# MAIN_BOARD_01.net
KiCad netlist of a schematic drawn in EAGLE
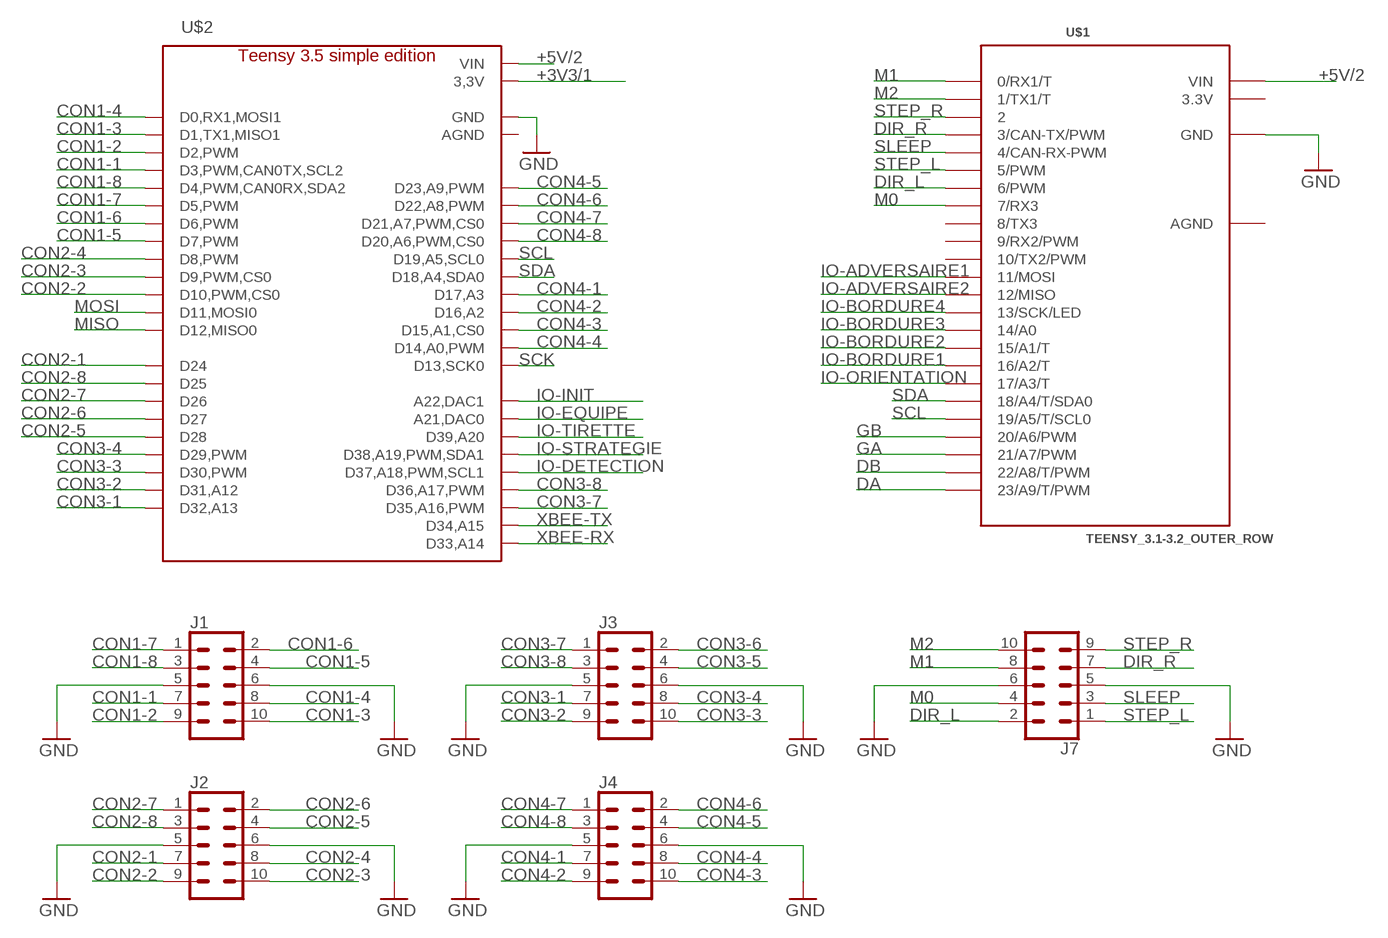
[diagram p0: schematic, sheet 1]
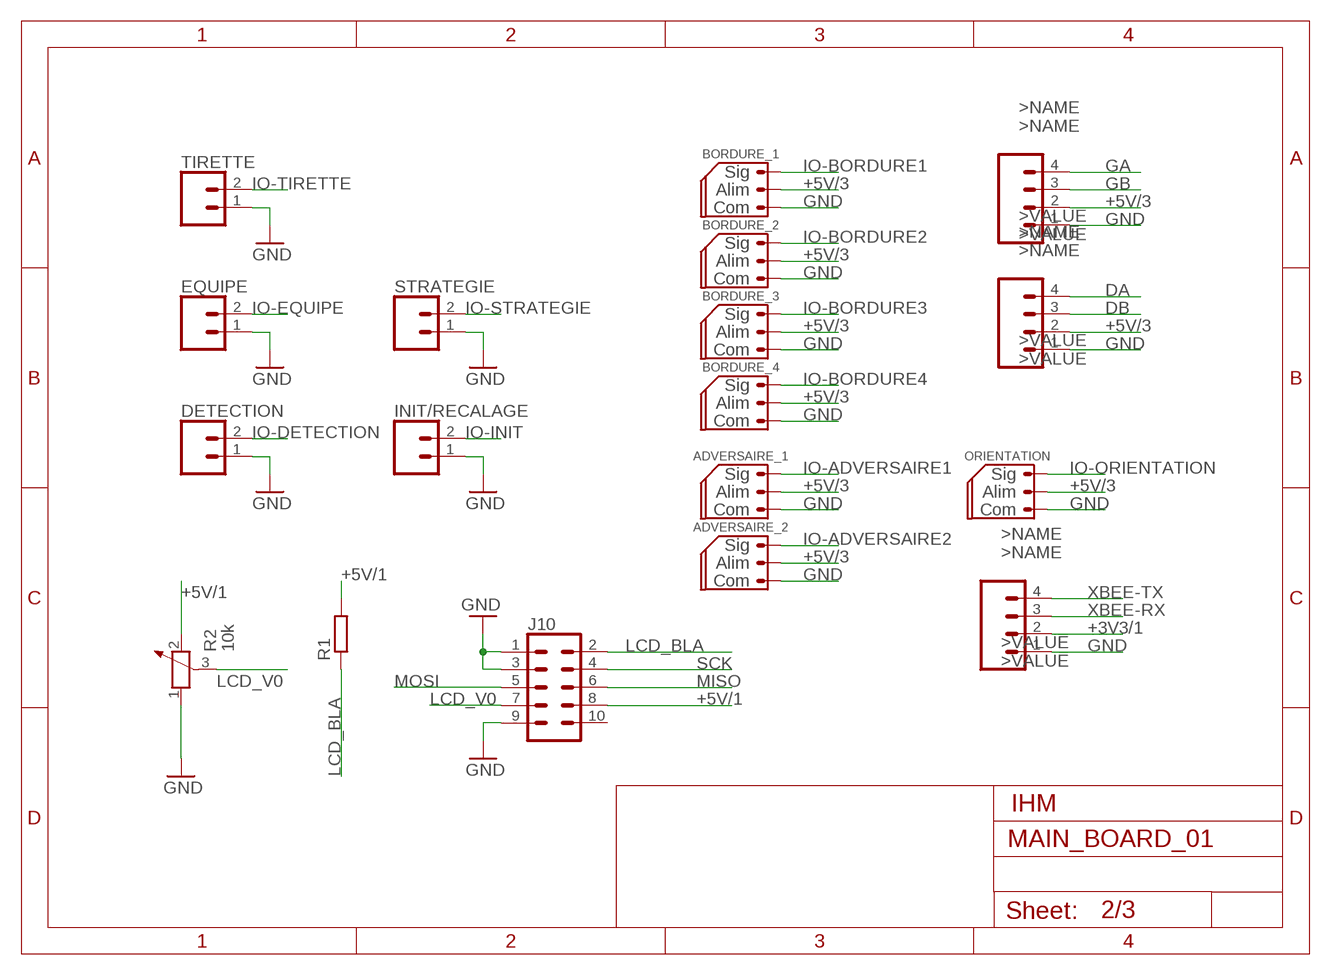
[diagram p1: schematic, sheet 2]
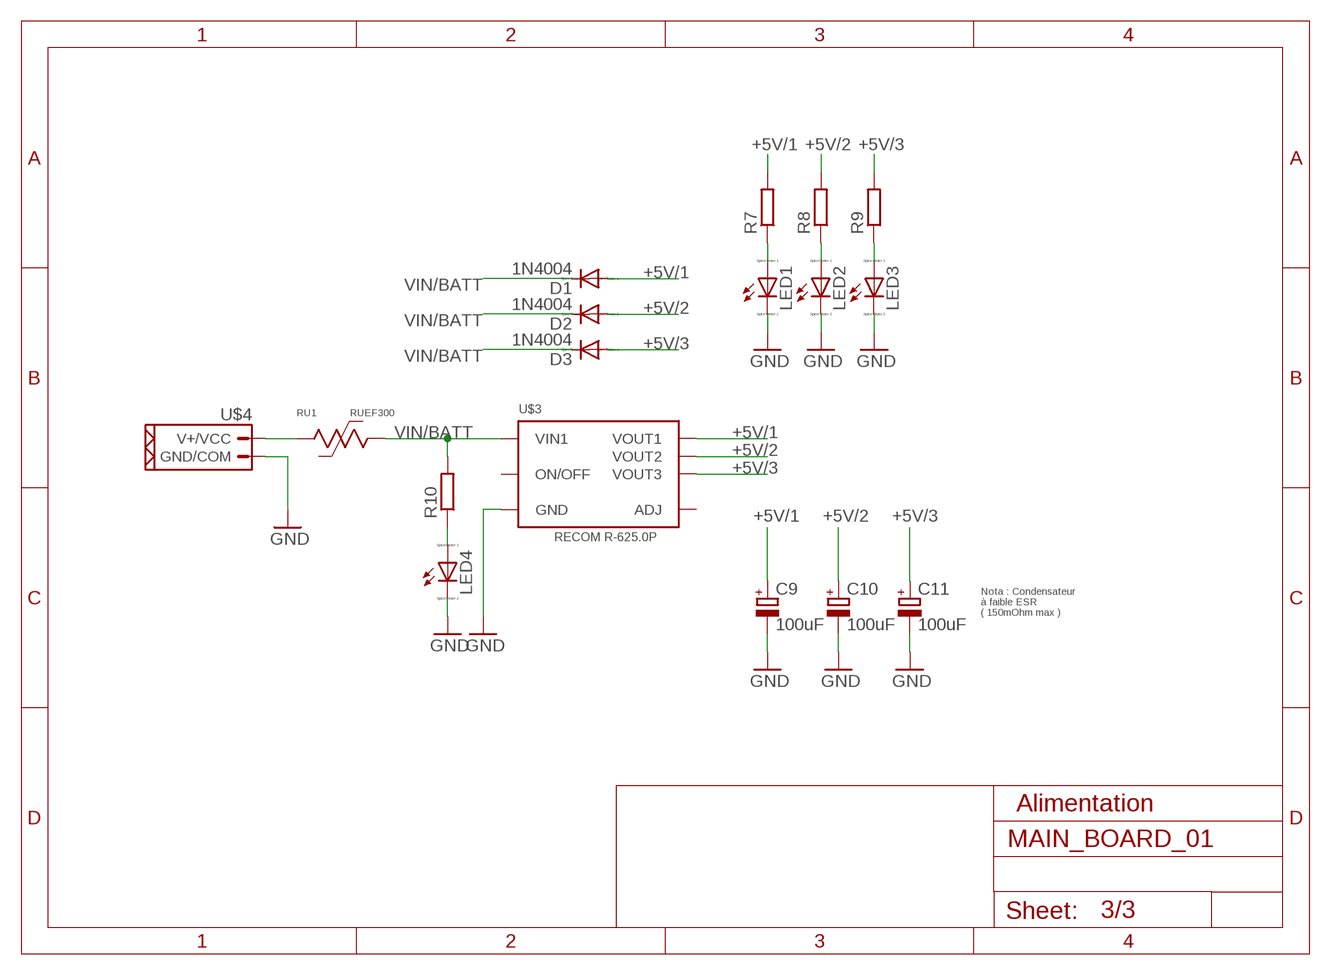
[diagram p2: schematic, sheet 3]

(export (version "E")
  (design (tool "Eeschema 10.0.6"))
  (components
    (comp (ref "J1")
      (value "CONN_05X2SHD")
      (footprint "eagle-import:2X5-SHROUDED")
      (libsource (lib "eagle-import") (part "CONN_05X2SHD"))
    )
    (comp (ref "J2")
      (value "CONN_05X2SHD")
      (footprint "eagle-import:2X5-SHROUDED")
      (libsource (lib "eagle-import") (part "CONN_05X2SHD"))
    )
    (comp (ref "J3")
      (value "CONN_05X2SHD")
      (footprint "eagle-import:2X5-SHROUDED")
      (libsource (lib "eagle-import") (part "CONN_05X2SHD"))
    )
    (comp (ref "J4")
      (value "CONN_05X2SHD")
      (footprint "eagle-import:2X5-SHROUDED")
      (libsource (lib "eagle-import") (part "CONN_05X2SHD"))
    )
    (comp (ref "J7")
      (value "CONN_05X2SHD")
      (footprint "eagle-import:2X5-SHROUDED")
      (libsource (lib "eagle-import") (part "CONN_05X2SHD"))
    )
    (comp (ref "U$1")
      (value "TEENSY_3.1-3.2_OUTER_ROW")
      (footprint "eagle-import:TEENSY_3.0-3.2&LC_OUTER_ROW")
      (libsource (lib "eagle-import") (part "TEENSY_3.1-3.2_OUTER_ROW"))
    )
    (comp (ref "U$2")
      (value "TEENSY_3.5")
      (footprint "eagle-import:TEENSY_3.5_LIGHT")
      (libsource (lib "eagle-import") (part "TEENSY_3.5"))
    )
    (comp (ref "C9")
      (value "100uF")
      (footprint "eagle-import:E5-10,5")
      (libsource (lib "eagle-import") (part "CPOL-EUE5-10.5"))
    )
    (comp (ref "C10")
      (value "100uF")
      (footprint "eagle-import:E5-10,5")
      (libsource (lib "eagle-import") (part "CPOL-EUE5-10.5"))
    )
    (comp (ref "C11")
      (value "100uF")
      (footprint "eagle-import:E5-10,5")
      (libsource (lib "eagle-import") (part "CPOL-EUE5-10.5"))
    )
    (comp (ref "D1")
      (value "1N4004")
      (footprint "eagle-import:DO41-10")
      (libsource (lib "eagle-import") (part "1N4004"))
    )
    (comp (ref "D2")
      (value "1N4004")
      (footprint "eagle-import:DO41-10")
      (libsource (lib "eagle-import") (part "1N4004"))
    )
    (comp (ref "D3")
      (value "1N4004")
      (footprint "eagle-import:DO41-10")
      (libsource (lib "eagle-import") (part "1N4004"))
    )
    (comp (ref "LED1")
      (value "LED_E")
      (footprint "eagle-import:LED_1206")
      (libsource (lib "eagle-import") (part "LED_E"))
    )
    (comp (ref "LED2")
      (value "LED_E")
      (footprint "eagle-import:LED_1206")
      (libsource (lib "eagle-import") (part "LED_E"))
    )
    (comp (ref "LED3")
      (value "LED_E")
      (footprint "eagle-import:LED_1206")
      (libsource (lib "eagle-import") (part "LED_E"))
    )
    (comp (ref "LED4")
      (value "LED_E")
      (footprint "eagle-import:LED_1206")
      (libsource (lib "eagle-import") (part "LED_E"))
    )
    (comp (ref "R7")
      (value "R-EU_R1206")
      (footprint "eagle-import:R1206")
      (libsource (lib "eagle-import") (part "R-EU_R1206"))
    )
    (comp (ref "R8")
      (value "R-EU_R1206")
      (footprint "eagle-import:R1206")
      (libsource (lib "eagle-import") (part "R-EU_R1206"))
    )
    (comp (ref "R9")
      (value "R-EU_R1206")
      (footprint "eagle-import:R1206")
      (libsource (lib "eagle-import") (part "R-EU_R1206"))
    )
    (comp (ref "R10")
      (value "R-EU_R1206")
      (footprint "eagle-import:R1206")
      (libsource (lib "eagle-import") (part "R-EU_R1206"))
    )
    (comp (ref "RU1")
      (value "RUEF300")
      (footprint "eagle-import:RUEF300")
      (libsource (lib "eagle-import") (part "RUEF300"))
    )
    (comp (ref "U$3")
      (value "R-625.0P")
      (footprint "eagle-import:R-6XXXP")
      (libsource (lib "eagle-import") (part "R-625.0P"))
    )
    (comp (ref "U$4")
      (value "CONN_02_PUI")
      (footprint "eagle-import:NSK396-2C")
      (libsource (lib "eagle-import") (part "CONN_02_PUI"))
    )
    (comp (ref "ADVERSAIRE_1")
      (value "CONN_03_SERVO")
      (footprint "eagle-import:MOLEX-1X3")
      (libsource (lib "eagle-import") (part "CONN_03_SERVO"))
    )
    (comp (ref "ADVERSAIRE_2")
      (value "CONN_03_SERVO")
      (footprint "eagle-import:MOLEX-1X3")
      (libsource (lib "eagle-import") (part "CONN_03_SERVO"))
    )
    (comp (ref "BORDURE_1")
      (value "CONN_03_SERVO")
      (footprint "eagle-import:MOLEX-1X3")
      (libsource (lib "eagle-import") (part "CONN_03_SERVO"))
    )
    (comp (ref "BORDURE_2")
      (value "CONN_03_SERVO")
      (footprint "eagle-import:MOLEX-1X3")
      (libsource (lib "eagle-import") (part "CONN_03_SERVO"))
    )
    (comp (ref "BORDURE_3")
      (value "CONN_03_SERVO")
      (footprint "eagle-import:MOLEX-1X3")
      (libsource (lib "eagle-import") (part "CONN_03_SERVO"))
    )
    (comp (ref "BORDURE_4")
      (value "CONN_03_SERVO")
      (footprint "eagle-import:MOLEX-1X3")
      (libsource (lib "eagle-import") (part "CONN_03_SERVO"))
    )
    (comp (ref "DETECTION")
      (value "CONN_02POLAR")
      (footprint "eagle-import:MOLEX-1X2")
      (libsource (lib "eagle-import") (part "CONN_02POLAR"))
    )
    (comp (ref "ENC_DROIT")
      (value "CONN_04POLAR")
      (footprint "eagle-import:MOLEX-1X4")
      (libsource (lib "eagle-import") (part "CONN_04POLAR"))
    )
    (comp (ref "ENC_DROIT1")
      (value "CONN_04POLAR")
      (footprint "eagle-import:MOLEX-1X4")
      (libsource (lib "eagle-import") (part "CONN_04POLAR"))
    )
    (comp (ref "ENC_GAUCHE")
      (value "CONN_04POLAR")
      (footprint "eagle-import:MOLEX-1X4")
      (libsource (lib "eagle-import") (part "CONN_04POLAR"))
    )
    (comp (ref "EQUIPE")
      (value "CONN_02POLAR")
      (footprint "eagle-import:MOLEX-1X2")
      (libsource (lib "eagle-import") (part "CONN_02POLAR"))
    )
    (comp (ref "INIT/RECALAGE")
      (value "CONN_02POLAR")
      (footprint "eagle-import:MOLEX-1X2")
      (libsource (lib "eagle-import") (part "CONN_02POLAR"))
    )
    (comp (ref "J10")
      (value "CONN_05X2SHD")
      (footprint "eagle-import:2X5-SHROUDED")
      (libsource (lib "eagle-import") (part "CONN_05X2SHD"))
    )
    (comp (ref "ORIENTATION")
      (value "CONN_03_SERVO")
      (footprint "eagle-import:MOLEX-1X3")
      (libsource (lib "eagle-import") (part "CONN_03_SERVO"))
    )
    (comp (ref "R1")
      (value "R-EU_R1206")
      (footprint "eagle-import:R1206")
      (libsource (lib "eagle-import") (part "R-EU_R1206"))
    )
    (comp (ref "R2")
      (value "10k")
      (footprint "eagle-import:PT-10")
      (libsource (lib "eagle-import") (part "POTENTIOMETER_PT-10"))
    )
    (comp (ref "STRATEGIE")
      (value "CONN_02POLAR")
      (footprint "eagle-import:MOLEX-1X2")
      (libsource (lib "eagle-import") (part "CONN_02POLAR"))
    )
    (comp (ref "TIRETTE")
      (value "CONN_02POLAR")
      (footprint "eagle-import:MOLEX-1X2")
      (libsource (lib "eagle-import") (part "CONN_02POLAR"))
    )
  )
  (nets
    (net (code "1") (name "+3V3{slash}1") (class "Default")
      (node (ref "ENC_DROIT1") (pin "2") (pinfunction "2_2") (pintype "passive"))
      (node (ref "U$2") (pin "P$15") (pinfunction "3,3V_P$15") (pintype "power_in"))
      (node (ref "U$2") (pin "P$46") (pinfunction "3,3V_P$46") (pintype "power_in"))
    )
    (net (code "2") (name "+5V{slash}1") (class "Default")
      (node (ref "C9") (pin "+") (pinfunction "+_+") (pintype "passive"))
      (node (ref "D1") (pin "A") (pinfunction "A_A") (pintype "passive"))
      (node (ref "J10") (pin "8") (pinfunction "8_8") (pintype "passive"))
      (node (ref "R1") (pin "2") (pinfunction "2_2") (pintype "passive"))
      (node (ref "R2") (pin "2") (pinfunction "2_2") (pintype "passive"))
      (node (ref "R7") (pin "2") (pinfunction "2_2") (pintype "passive"))
      (node (ref "U$3") (pin "P$9") (pinfunction "VOUT1_P$9") (pintype "power_in"))
    )
    (net (code "3") (name "+5V{slash}2") (class "Default")
      (node (ref "C10") (pin "+") (pinfunction "+_+") (pintype "passive"))
      (node (ref "D2") (pin "A") (pinfunction "A_A") (pintype "passive"))
      (node (ref "R8") (pin "2") (pinfunction "2_2") (pintype "passive"))
      (node (ref "U$1") (pin "V_IN") (pinfunction "VIN_V_IN") (pintype "power_in"))
      (node (ref "U$2") (pin "P$48") (pinfunction "VIN_P$48") (pintype "passive"))
      (node (ref "U$3") (pin "P$10") (pinfunction "VOUT2_P$10") (pintype "power_in"))
    )
    (net (code "4") (name "+5V{slash}3") (class "Default")
      (node (ref "ADVERSAIRE_1") (pin "2") (pinfunction "2_2") (pintype "passive"))
      (node (ref "ADVERSAIRE_2") (pin "2") (pinfunction "2_2") (pintype "passive"))
      (node (ref "BORDURE_1") (pin "2") (pinfunction "2_2") (pintype "passive"))
      (node (ref "BORDURE_2") (pin "2") (pinfunction "2_2") (pintype "passive"))
      (node (ref "BORDURE_3") (pin "2") (pinfunction "2_2") (pintype "passive"))
      (node (ref "BORDURE_4") (pin "2") (pinfunction "2_2") (pintype "passive"))
      (node (ref "C11") (pin "+") (pinfunction "+_+") (pintype "passive"))
      (node (ref "D3") (pin "A") (pinfunction "A_A") (pintype "passive"))
      (node (ref "ENC_DROIT") (pin "2") (pinfunction "2_2") (pintype "passive"))
      (node (ref "ENC_GAUCHE") (pin "2") (pinfunction "2_2") (pintype "passive"))
      (node (ref "ORIENTATION") (pin "2") (pinfunction "2_2") (pintype "passive"))
      (node (ref "R9") (pin "2") (pinfunction "2_2") (pintype "passive"))
      (node (ref "U$3") (pin "P$11") (pinfunction "VOUT3_P$11") (pintype "power_in"))
    )
    (net (code "5") (name "3.3V") (class "Default")
      (node (ref "U$1") (pin "3.3V") (pinfunction "3.3V_3.3V") (pintype "power_in"))
    )
    (net (code "6") (name "ADJ") (class "Default")
      (node (ref "U$3") (pin "P$12") (pinfunction "ADJ_P$12") (pintype "power_in"))
    )
    (net (code "7") (name "AGND") (class "Default")
      (node (ref "U$1") (pin "AGND") (pinfunction "AGND_AGND") (pintype "power_in"))
    )
    (net (code "8") (name "CON1-1") (class "Default")
      (node (ref "J1") (pin "7") (pinfunction "7_7") (pintype "passive"))
      (node (ref "U$2") (pin "P$5") (pinfunction "D3,PWM,CAN0TX,SCL2_P$5") (pintype "passive"))
    )
    (net (code "9") (name "CON1-2") (class "Default")
      (node (ref "J1") (pin "9") (pinfunction "9_9") (pintype "passive"))
      (node (ref "U$2") (pin "P$4") (pinfunction "D2,PWM_P$4") (pintype "passive"))
    )
    (net (code "10") (name "CON1-3") (class "Default")
      (node (ref "J1") (pin "10") (pinfunction "10_10") (pintype "passive"))
      (node (ref "U$2") (pin "P$3") (pinfunction "D1,TX1,MISO1_P$3") (pintype "passive"))
    )
    (net (code "11") (name "CON1-4") (class "Default")
      (node (ref "J1") (pin "8") (pinfunction "8_8") (pintype "passive"))
      (node (ref "U$2") (pin "P$2") (pinfunction "D0,RX1,MOSI1_P$2") (pintype "passive"))
    )
    (net (code "12") (name "CON1-5") (class "Default")
      (node (ref "J1") (pin "4") (pinfunction "4_4") (pintype "passive"))
      (node (ref "U$2") (pin "P$9") (pinfunction "D7,PWM_P$9") (pintype "passive"))
    )
    (net (code "13") (name "CON1-6") (class "Default")
      (node (ref "J1") (pin "2") (pinfunction "2_2") (pintype "passive"))
      (node (ref "U$2") (pin "P$8") (pinfunction "D6,PWM_P$8") (pintype "passive"))
    )
    (net (code "14") (name "CON1-7") (class "Default")
      (node (ref "J1") (pin "1") (pinfunction "1_1") (pintype "passive"))
      (node (ref "U$2") (pin "P$7") (pinfunction "D5,PWM_P$7") (pintype "passive"))
    )
    (net (code "15") (name "CON1-8") (class "Default")
      (node (ref "J1") (pin "3") (pinfunction "3_3") (pintype "passive"))
      (node (ref "U$2") (pin "P$6") (pinfunction "D4,PWM,CAN0RX,SDA2_P$6") (pintype "passive"))
    )
    (net (code "16") (name "CON2-1") (class "Default")
      (node (ref "J2") (pin "7") (pinfunction "7_7") (pintype "passive"))
      (node (ref "U$2") (pin "P$16") (pinfunction "D24_P$16") (pintype "passive"))
    )
    (net (code "17") (name "CON2-2") (class "Default")
      (node (ref "J2") (pin "9") (pinfunction "9_9") (pintype "passive"))
      (node (ref "U$2") (pin "P$12") (pinfunction "D10,PWM,CS0_P$12") (pintype "passive"))
    )
    (net (code "18") (name "CON2-3") (class "Default")
      (node (ref "J2") (pin "10") (pinfunction "10_10") (pintype "passive"))
      (node (ref "U$2") (pin "P$11") (pinfunction "D9,PWM,CS0_P$11") (pintype "passive"))
    )
    (net (code "19") (name "CON2-4") (class "Default")
      (node (ref "J2") (pin "8") (pinfunction "8_8") (pintype "passive"))
      (node (ref "U$2") (pin "P$10") (pinfunction "D8,PWM_P$10") (pintype "passive"))
    )
    (net (code "20") (name "CON2-5") (class "Default")
      (node (ref "J2") (pin "4") (pinfunction "4_4") (pintype "passive"))
      (node (ref "U$2") (pin "P$20") (pinfunction "D28_P$20") (pintype "passive"))
    )
    (net (code "21") (name "CON2-6") (class "Default")
      (node (ref "J2") (pin "2") (pinfunction "2_2") (pintype "passive"))
      (node (ref "U$2") (pin "P$19") (pinfunction "D27_P$19") (pintype "passive"))
    )
    (net (code "22") (name "CON2-7") (class "Default")
      (node (ref "J2") (pin "1") (pinfunction "1_1") (pintype "passive"))
      (node (ref "U$2") (pin "P$18") (pinfunction "D26_P$18") (pintype "passive"))
    )
    (net (code "23") (name "CON2-8") (class "Default")
      (node (ref "J2") (pin "3") (pinfunction "3_3") (pintype "passive"))
      (node (ref "U$2") (pin "P$17") (pinfunction "D25_P$17") (pintype "passive"))
    )
    (net (code "24") (name "CON3-1") (class "Default")
      (node (ref "J3") (pin "7") (pinfunction "7_7") (pintype "passive"))
      (node (ref "U$2") (pin "P$24") (pinfunction "D32,A13_P$24") (pintype "passive"))
    )
    (net (code "25") (name "CON3-2") (class "Default")
      (node (ref "J3") (pin "9") (pinfunction "9_9") (pintype "passive"))
      (node (ref "U$2") (pin "P$23") (pinfunction "D31,A12_P$23") (pintype "passive"))
    )
    (net (code "26") (name "CON3-3") (class "Default")
      (node (ref "J3") (pin "10") (pinfunction "10_10") (pintype "passive"))
      (node (ref "U$2") (pin "P$22") (pinfunction "D30,PWM_P$22") (pintype "passive"))
    )
    (net (code "27") (name "CON3-4") (class "Default")
      (node (ref "J3") (pin "8") (pinfunction "8_8") (pintype "passive"))
      (node (ref "U$2") (pin "P$21") (pinfunction "D29,PWM_P$21") (pintype "passive"))
    )
    (net (code "28") (name "CON3-5") (class "Default")
      (node (ref "J3") (pin "4") (pinfunction "4_4") (pintype "passive"))
    )
    (net (code "29") (name "CON3-6") (class "Default")
      (node (ref "J3") (pin "2") (pinfunction "2_2") (pintype "passive"))
    )
    (net (code "30") (name "CON3-7") (class "Default")
      (node (ref "J3") (pin "1") (pinfunction "1_1") (pintype "passive"))
      (node (ref "U$2") (pin "P$27") (pinfunction "D35,A16,PWM_P$27") (pintype "passive"))
    )
    (net (code "31") (name "CON3-8") (class "Default")
      (node (ref "J3") (pin "3") (pinfunction "3_3") (pintype "passive"))
      (node (ref "U$2") (pin "P$28") (pinfunction "D36,A17,PWM_P$28") (pintype "passive"))
    )
    (net (code "32") (name "CON4-1") (class "Default")
      (node (ref "J4") (pin "7") (pinfunction "7_7") (pintype "passive"))
      (node (ref "U$2") (pin "P$39") (pinfunction "D17,A3_P$39") (pintype "passive"))
    )
    (net (code "33") (name "CON4-2") (class "Default")
      (node (ref "J4") (pin "9") (pinfunction "9_9") (pintype "passive"))
      (node (ref "U$2") (pin "P$38") (pinfunction "D16,A2_P$38") (pintype "passive"))
    )
    (net (code "34") (name "CON4-3") (class "Default")
      (node (ref "J4") (pin "10") (pinfunction "10_10") (pintype "passive"))
      (node (ref "U$2") (pin "P$37") (pinfunction "D15,A1,CS0_P$37") (pintype "passive"))
    )
    (net (code "35") (name "CON4-4") (class "Default")
      (node (ref "J4") (pin "8") (pinfunction "8_8") (pintype "passive"))
      (node (ref "U$2") (pin "P$36") (pinfunction "D14,A0,PWM_P$36") (pintype "passive"))
    )
    (net (code "36") (name "CON4-5") (class "Default")
      (node (ref "J4") (pin "4") (pinfunction "4_4") (pintype "passive"))
      (node (ref "U$2") (pin "P$45") (pinfunction "D23,A9,PWM_P$45") (pintype "passive"))
    )
    (net (code "37") (name "CON4-6") (class "Default")
      (node (ref "J4") (pin "2") (pinfunction "2_2") (pintype "passive"))
      (node (ref "U$2") (pin "P$44") (pinfunction "D22,A8,PWM_P$44") (pintype "passive"))
    )
    (net (code "38") (name "CON4-7") (class "Default")
      (node (ref "J4") (pin "1") (pinfunction "1_1") (pintype "passive"))
      (node (ref "U$2") (pin "P$43") (pinfunction "D21,A7,PWM,CS0_P$43") (pintype "passive"))
    )
    (net (code "39") (name "CON4-8") (class "Default")
      (node (ref "J4") (pin "3") (pinfunction "3_3") (pintype "passive"))
      (node (ref "U$2") (pin "P$42") (pinfunction "D20,A6,PWM,CS0_P$42") (pintype "passive"))
    )
    (net (code "40") (name "DA") (class "Default")
      (node (ref "ENC_DROIT") (pin "4") (pinfunction "4_4") (pintype "passive"))
      (node (ref "U$1") (pin "23/A9") (pinfunction "23/A9/T/PWM_23/A9") (pintype "bidirectional"))
    )
    (net (code "41") (name "DB") (class "Default")
      (node (ref "ENC_DROIT") (pin "3") (pinfunction "3_3") (pintype "passive"))
      (node (ref "U$1") (pin "22/A8") (pinfunction "22/A8/T/PWM_22/A8") (pintype "bidirectional"))
    )
    (net (code "42") (name "DIR_L") (class "Default")
      (node (ref "J7") (pin "2") (pinfunction "2_2") (pintype "passive"))
      (node (ref "U$1") (pin "6") (pinfunction "6/PWM_6") (pintype "bidirectional"))
    )
    (net (code "43") (name "DIR_R") (class "Default")
      (node (ref "J7") (pin "7") (pinfunction "7_7") (pintype "passive"))
      (node (ref "U$1") (pin "3") (pinfunction "3/CAN-TX/PWM_3") (pintype "bidirectional"))
    )
    (net (code "44") (name "GA") (class "Default")
      (node (ref "ENC_GAUCHE") (pin "4") (pinfunction "4_4") (pintype "passive"))
      (node (ref "U$1") (pin "21/A7") (pinfunction "21/A7/PWM_21/A7") (pintype "bidirectional"))
    )
    (net (code "45") (name "GB") (class "Default")
      (node (ref "ENC_GAUCHE") (pin "3") (pinfunction "3_3") (pintype "passive"))
      (node (ref "U$1") (pin "20/A6") (pinfunction "20/A6/PWM_20/A6") (pintype "bidirectional"))
    )
    (net (code "46") (name "GND") (class "Default")
      (node (ref "ADVERSAIRE_1") (pin "1") (pinfunction "1_1") (pintype "passive"))
      (node (ref "ADVERSAIRE_2") (pin "1") (pinfunction "1_1") (pintype "passive"))
      (node (ref "BORDURE_1") (pin "1") (pinfunction "1_1") (pintype "passive"))
      (node (ref "BORDURE_2") (pin "1") (pinfunction "1_1") (pintype "passive"))
      (node (ref "BORDURE_3") (pin "1") (pinfunction "1_1") (pintype "passive"))
      (node (ref "BORDURE_4") (pin "1") (pinfunction "1_1") (pintype "passive"))
      (node (ref "C10") (pin "-") (pinfunction "-_-") (pintype "passive"))
      (node (ref "C11") (pin "-") (pinfunction "-_-") (pintype "passive"))
      (node (ref "C9") (pin "-") (pinfunction "-_-") (pintype "passive"))
      (node (ref "DETECTION") (pin "1") (pinfunction "1_1") (pintype "passive"))
      (node (ref "ENC_DROIT") (pin "1") (pinfunction "1_1") (pintype "passive"))
      (node (ref "ENC_DROIT1") (pin "1") (pinfunction "1_1") (pintype "passive"))
      (node (ref "ENC_GAUCHE") (pin "1") (pinfunction "1_1") (pintype "passive"))
      (node (ref "EQUIPE") (pin "1") (pinfunction "1_1") (pintype "passive"))
      (node (ref "INIT/RECALAGE") (pin "1") (pinfunction "1_1") (pintype "passive"))
      (node (ref "J1") (pin "5") (pinfunction "5_5") (pintype "passive"))
      (node (ref "J1") (pin "6") (pinfunction "6_6") (pintype "passive"))
      (node (ref "J10") (pin "1") (pinfunction "1_1") (pintype "passive"))
      (node (ref "J10") (pin "3") (pinfunction "3_3") (pintype "passive"))
      (node (ref "J10") (pin "9") (pinfunction "9_9") (pintype "passive"))
      (node (ref "J2") (pin "5") (pinfunction "5_5") (pintype "passive"))
      (node (ref "J2") (pin "6") (pinfunction "6_6") (pintype "passive"))
      (node (ref "J3") (pin "5") (pinfunction "5_5") (pintype "passive"))
      (node (ref "J3") (pin "6") (pinfunction "6_6") (pintype "passive"))
      (node (ref "J4") (pin "5") (pinfunction "5_5") (pintype "passive"))
      (node (ref "J4") (pin "6") (pinfunction "6_6") (pintype "passive"))
      (node (ref "J7") (pin "5") (pinfunction "5_5") (pintype "passive"))
      (node (ref "J7") (pin "6") (pinfunction "6_6") (pintype "passive"))
      (node (ref "LED1") (pin "C") (pinfunction "C_C") (pintype "passive"))
      (node (ref "LED2") (pin "C") (pinfunction "C_C") (pintype "passive"))
      (node (ref "LED3") (pin "C") (pinfunction "C_C") (pintype "passive"))
      (node (ref "LED4") (pin "C") (pinfunction "C_C") (pintype "passive"))
      (node (ref "ORIENTATION") (pin "1") (pinfunction "1_1") (pintype "passive"))
      (node (ref "R2") (pin "1") (pinfunction "1_1") (pintype "passive"))
      (node (ref "STRATEGIE") (pin "1") (pinfunction "1_1") (pintype "passive"))
      (node (ref "TIRETTE") (pin "1") (pinfunction "1_1") (pintype "passive"))
      (node (ref "U$1") (pin "GND") (pinfunction "GND_GND") (pintype "power_in"))
      (node (ref "U$2") (pin "GND") (pinfunction "GND_GND") (pintype "power_in"))
      (node (ref "U$2") (pin "P$34") (pinfunction "GND_P$34") (pintype "power_in"))
      (node (ref "U$3") (pin "P$5") (pinfunction "GND_P$5") (pintype "power_in"))
      (node (ref "U$3") (pin "P$6") (pinfunction "GND_P$6") (pintype "power_in"))
      (node (ref "U$3") (pin "P$7") (pinfunction "GND_P$7") (pintype "power_in"))
      (node (ref "U$3") (pin "P$8") (pinfunction "GND_P$8") (pintype "power_in"))
      (node (ref "U$4") (pin "P$1") (pinfunction "GND/COM_P$1") (pintype "passive"))
    )
    (net (code "47") (name "IO-ADVERSAIRE1") (class "Default")
      (node (ref "ADVERSAIRE_1") (pin "3") (pinfunction "3_3") (pintype "passive"))
      (node (ref "U$1") (pin "11") (pinfunction "11/MOSI_11") (pintype "bidirectional"))
    )
    (net (code "48") (name "IO-ADVERSAIRE2") (class "Default")
      (node (ref "ADVERSAIRE_2") (pin "3") (pinfunction "3_3") (pintype "passive"))
      (node (ref "U$1") (pin "12") (pinfunction "12/MISO_12") (pintype "bidirectional"))
    )
    (net (code "49") (name "IO-BORDURE1") (class "Default")
      (node (ref "BORDURE_1") (pin "3") (pinfunction "3_3") (pintype "passive"))
      (node (ref "U$1") (pin "16/A2") (pinfunction "16/A2/T_16/A2") (pintype "bidirectional"))
    )
    (net (code "50") (name "IO-BORDURE2") (class "Default")
      (node (ref "BORDURE_2") (pin "3") (pinfunction "3_3") (pintype "passive"))
      (node (ref "U$1") (pin "15/A1") (pinfunction "15/A1/T_15/A1") (pintype "bidirectional"))
    )
    (net (code "51") (name "IO-BORDURE3") (class "Default")
      (node (ref "BORDURE_3") (pin "3") (pinfunction "3_3") (pintype "passive"))
      (node (ref "U$1") (pin "14/A0") (pinfunction "14/A0_14/A0") (pintype "bidirectional"))
    )
    (net (code "52") (name "IO-BORDURE4") (class "Default")
      (node (ref "BORDURE_4") (pin "3") (pinfunction "3_3") (pintype "passive"))
      (node (ref "U$1") (pin "13") (pinfunction "13/SCK/LED_13") (pintype "bidirectional"))
    )
    (net (code "53") (name "IO-DETECTION") (class "Default")
      (node (ref "DETECTION") (pin "2") (pinfunction "2_2") (pintype "passive"))
      (node (ref "U$2") (pin "P$29") (pinfunction "D37,A18,PWM,SCL1_P$29") (pintype "passive"))
    )
    (net (code "54") (name "IO-EQUIPE") (class "Default")
      (node (ref "EQUIPE") (pin "2") (pinfunction "2_2") (pintype "passive"))
      (node (ref "U$2") (pin "P$32") (pinfunction "A21,DAC0_P$32") (pintype "passive"))
    )
    (net (code "55") (name "IO-INIT") (class "Default")
      (node (ref "INIT/RECALAGE") (pin "2") (pinfunction "2_2") (pintype "passive"))
      (node (ref "U$2") (pin "P$33") (pinfunction "A22,DAC1_P$33") (pintype "passive"))
    )
    (net (code "56") (name "IO-ORIENTATION") (class "Default")
      (node (ref "ORIENTATION") (pin "3") (pinfunction "3_3") (pintype "passive"))
      (node (ref "U$1") (pin "17/A3") (pinfunction "17/A3/T_17/A3") (pintype "bidirectional"))
    )
    (net (code "57") (name "IO-STRATEGIE") (class "Default")
      (node (ref "STRATEGIE") (pin "2") (pinfunction "2_2") (pintype "passive"))
      (node (ref "U$2") (pin "P$30") (pinfunction "D38,A19,PWM,SDA1_P$30") (pintype "passive"))
    )
    (net (code "58") (name "IO-TIRETTE") (class "Default")
      (node (ref "TIRETTE") (pin "2") (pinfunction "2_2") (pintype "passive"))
      (node (ref "U$2") (pin "P$31") (pinfunction "D39,A20_P$31") (pintype "passive"))
    )
    (net (code "59") (name "LCD_BLA") (class "Default")
      (node (ref "J10") (pin "2") (pinfunction "2_2") (pintype "passive"))
      (node (ref "R1") (pin "1") (pinfunction "1_1") (pintype "passive"))
    )
    (net (code "60") (name "LCD_V0") (class "Default")
      (node (ref "J10") (pin "7") (pinfunction "7_7") (pintype "passive"))
      (node (ref "R2") (pin "3") (pinfunction "3_3") (pintype "passive"))
    )
    (net (code "61") (name "M0") (class "Default")
      (node (ref "J7") (pin "4") (pinfunction "4_4") (pintype "passive"))
      (node (ref "U$1") (pin "7") (pinfunction "7/RX3_7") (pintype "bidirectional"))
    )
    (net (code "62") (name "M1") (class "Default")
      (node (ref "J7") (pin "8") (pinfunction "8_8") (pintype "passive"))
      (node (ref "U$1") (pin "0") (pinfunction "0/RX1/T_0") (pintype "bidirectional"))
    )
    (net (code "63") (name "M2") (class "Default")
      (node (ref "J7") (pin "10") (pinfunction "10_10") (pintype "passive"))
      (node (ref "U$1") (pin "1") (pinfunction "1/TX1/T_1") (pintype "bidirectional"))
    )
    (net (code "64") (name "MISO") (class "Default")
      (node (ref "J10") (pin "6") (pinfunction "6_6") (pintype "passive"))
      (node (ref "U$2") (pin "P$14") (pinfunction "D12,MISO0_P$14") (pintype "passive"))
    )
    (net (code "65") (name "MOSI") (class "Default")
      (node (ref "J10") (pin "5") (pinfunction "5_5") (pintype "passive"))
      (node (ref "U$2") (pin "P$13") (pinfunction "D11,MOSI0_P$13") (pintype "passive"))
    )
    (net (code "66") (name "Net-(LED1-PadA)") (class "Default")
      (node (ref "LED1") (pin "A") (pinfunction "A_A") (pintype "passive"))
      (node (ref "R7") (pin "1") (pinfunction "1_1") (pintype "passive"))
    )
    (net (code "67") (name "Net-(LED2-PadA)") (class "Default")
      (node (ref "LED2") (pin "A") (pinfunction "A_A") (pintype "passive"))
      (node (ref "R8") (pin "1") (pinfunction "1_1") (pintype "passive"))
    )
    (net (code "68") (name "Net-(LED3-PadA)") (class "Default")
      (node (ref "LED3") (pin "A") (pinfunction "A_A") (pintype "passive"))
      (node (ref "R9") (pin "1") (pinfunction "1_1") (pintype "passive"))
    )
    (net (code "69") (name "Net-(LED4-PadA)") (class "Default")
      (node (ref "LED4") (pin "A") (pinfunction "A_A") (pintype "passive"))
      (node (ref "R10") (pin "1") (pinfunction "1_1") (pintype "passive"))
    )
    (net (code "70") (name "Net-(U$4-V+{slash}VCC)") (class "Default")
      (node (ref "RU1") (pin "P$1") (pinfunction "P$1_P$1") (pintype "passive"))
      (node (ref "U$4") (pin "P$2") (pinfunction "V+/VCC_P$2") (pintype "passive"))
    )
    (net (code "71") (name "SCK") (class "Default")
      (node (ref "J10") (pin "4") (pinfunction "4_4") (pintype "passive"))
      (node (ref "U$2") (pin "P$35") (pinfunction "D13,SCK0_P$35") (pintype "passive"))
    )
    (net (code "72") (name "SCL") (class "Default")
      (node (ref "U$1") (pin "19/A5") (pinfunction "19/A5/T/SCL0_19/A5") (pintype "bidirectional"))
      (node (ref "U$2") (pin "P$41") (pinfunction "D19,A5,SCL0_P$41") (pintype "passive"))
    )
    (net (code "73") (name "SDA") (class "Default")
      (node (ref "U$1") (pin "18/A4") (pinfunction "18/A4/T/SDA0_18/A4") (pintype "bidirectional"))
      (node (ref "U$2") (pin "P$40") (pinfunction "D18,A4,SDA0_P$40") (pintype "passive"))
    )
    (net (code "74") (name "SLEEP") (class "Default")
      (node (ref "J7") (pin "3") (pinfunction "3_3") (pintype "passive"))
      (node (ref "U$1") (pin "4") (pinfunction "4/CAN-RX-PWM_4") (pintype "bidirectional"))
    )
    (net (code "75") (name "STEP_L") (class "Default")
      (node (ref "J7") (pin "1") (pinfunction "1_1") (pintype "passive"))
      (node (ref "U$1") (pin "5") (pinfunction "5/PWM_5") (pintype "bidirectional"))
    )
    (net (code "76") (name "STEP_R") (class "Default")
      (node (ref "J7") (pin "9") (pinfunction "9_9") (pintype "passive"))
      (node (ref "U$1") (pin "2") (pinfunction "2_2") (pintype "bidirectional"))
    )
    (net (code "77") (name "VIN{slash}BATT") (class "Default")
      (node (ref "D1") (pin "C") (pinfunction "C_C") (pintype "passive"))
      (node (ref "D2") (pin "C") (pinfunction "C_C") (pintype "passive"))
      (node (ref "D3") (pin "C") (pinfunction "C_C") (pintype "passive"))
      (node (ref "R10") (pin "2") (pinfunction "2_2") (pintype "passive"))
      (node (ref "RU1") (pin "P$2") (pinfunction "P$2_P$2") (pintype "passive"))
      (node (ref "U$3") (pin "P$2") (pinfunction "VIN1_P$2") (pintype "power_in"))
      (node (ref "U$3") (pin "P$3") (pinfunction "VIN1_P$3") (pintype "power_in"))
      (node (ref "U$3") (pin "P$4") (pinfunction "VIN1_P$4") (pintype "power_in"))
    )
    (net (code "78") (name "XBEE-RX") (class "Default")
      (node (ref "ENC_DROIT1") (pin "3") (pinfunction "3_3") (pintype "passive"))
      (node (ref "U$2") (pin "P$25") (pinfunction "D33,A14_P$25") (pintype "passive"))
    )
    (net (code "79") (name "XBEE-TX") (class "Default")
      (node (ref "ENC_DROIT1") (pin "4") (pinfunction "4_4") (pintype "passive"))
      (node (ref "U$2") (pin "P$26") (pinfunction "D34,A15_P$26") (pintype "passive"))
    )
    (net (code "80") (name "unconnected-(J10-Pad10)") (class "Default")
      (node (ref "J10") (pin "10") (pinfunction "10_10") (pintype "passive"))
    )
    (net (code "81") (name "unconnected-(U$1-8{slash}TX3-Pad8)") (class "Default")
      (node (ref "U$1") (pin "8") (pinfunction "8/TX3_8") (pintype "bidirectional"))
    )
    (net (code "82") (name "unconnected-(U$1-9{slash}RX2{slash}PWM-Pad9)") (class "Default")
      (node (ref "U$1") (pin "9") (pinfunction "9/RX2/PWM_9") (pintype "bidirectional"))
    )
    (net (code "83") (name "unconnected-(U$1-10{slash}TX2{slash}PWM-Pad10)") (class "Default")
      (node (ref "U$1") (pin "10") (pinfunction "10/TX2/PWM_10") (pintype "bidirectional"))
    )
    (net (code "84") (name "unconnected-(U$2-AGND-PadP$47)") (class "Default")
      (node (ref "U$2") (pin "P$47") (pinfunction "AGND_P$47") (pintype "passive"))
    )
    (net (code "85") (name "unconnected-(U$3-ON{slash}OFF-PadP$1)") (class "Default")
      (node (ref "U$3") (pin "P$1") (pinfunction "ON/OFF_P$1") (pintype "passive"))
    )
  )
)
